# main.net
KiCad netlist of a schematic drawn in Altium Designer
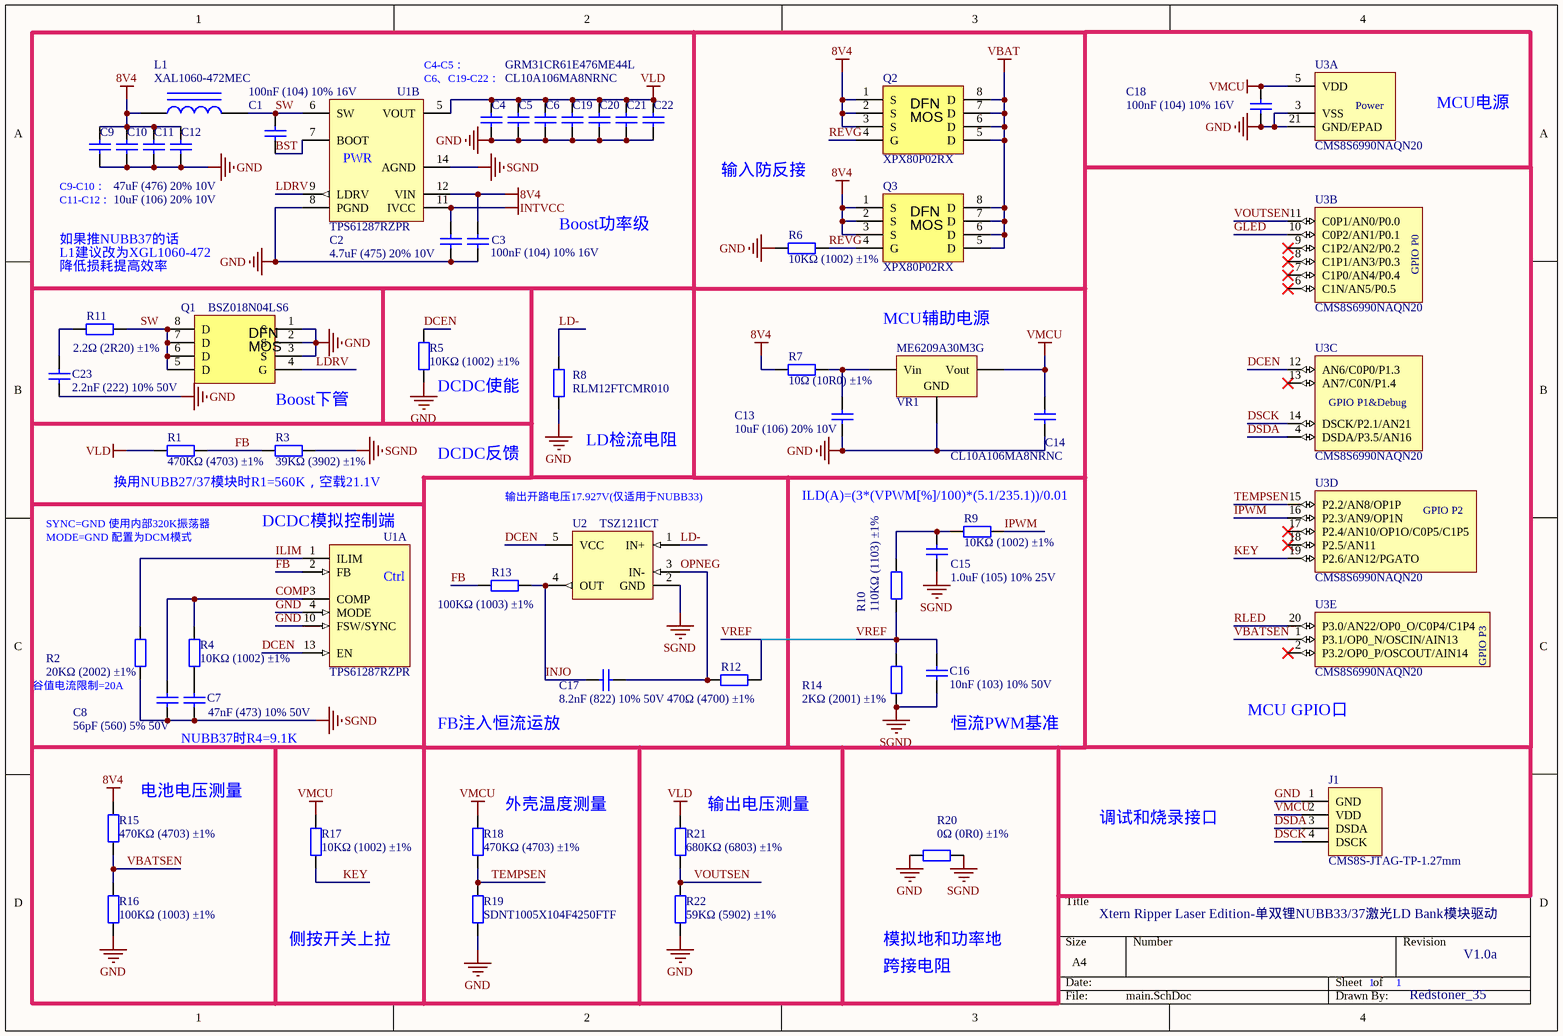
[diagram p0: main.SchDoc]

(export (version "E")
  (design (tool "Eeschema 10.0.6"))
  (components
    (comp (ref "C1")
      (value "100nF (104) 10% 16V")
      (footprint "0402_C")
      (description "贴片电容")
      (libsource (lib "Miscellaneous Devices LC") (part "0402 100nF (104) 10% 16V"))
    )
    (comp (ref "C2")
      (value "4.7uF (475) 20% 10V")
      (footprint "0402_C")
      (description "贴片电容")
      (libsource (lib "Miscellaneous Devices LC") (part "0402 4.7uF (475) 20% 10V"))
    )
    (comp (ref "C3")
      (value "100nF (104) 10% 16V")
      (footprint "0402_C")
      (description "贴片电容")
      (libsource (lib "Miscellaneous Devices LC") (part "0402 100nF (104) 10% 16V"))
    )
    (comp (ref "C4")
      (value "GRM31CR61E476ME44L")
      (footprint "1206C")
      (description "村田1206 MLCC 25V 47uF± 20% X5R")
      (fields (field (name "PUBLISHER") "Altium Limited"))
      (libsource (lib "山猫的集成库20190318") (part "Cap"))
    )
    (comp (ref "C5")
      (value "GRM31CR61E476ME44L")
      (footprint "1206C")
      (description "村田1206 MLCC 25V 47uF± 20% X5R")
      (fields (field (name "PUBLISHER") "Altium Limited"))
      (libsource (lib "山猫的集成库20190318") (part "Cap"))
    )
    (comp (ref "C6")
      (value "CL10A106MA8NRNC")
      (footprint "0603_C")
      (description "三星MLCC X5R 10uF ±20% 25V 0603封装")
      (libsource (lib "Miscellaneous Devices LC") (part "0603 10uF (106) 10% 10V"))
    )
    (comp (ref "C7")
      (value "47nF (473) 10% 50V")
      (footprint "0402_C")
      (description "贴片电容")
      (libsource (lib "Miscellaneous Devices LC") (part "0402 100nF (104) 10% 16V"))
    )
    (comp (ref "C8")
      (value "56pF (560) 5% 50V")
      (footprint "0402_C")
      (description "贴片电容")
      (libsource (lib "Miscellaneous Devices LC") (part "0402 56pF (560) 5% 50V"))
    )
    (comp (ref "C9")
      (value "10uF (106) 20% 10V")
      (footprint "0402_C")
      (description "贴片电容")
      (libsource (lib "Miscellaneous Devices LC") (part "0402 10uF (106) 20% 6.3V"))
    )
    (comp (ref "C10")
      (value "10uF (106) 20% 10V")
      (footprint "0402_C")
      (description "贴片电容")
      (libsource (lib "Miscellaneous Devices LC") (part "0402 10uF (106) 20% 6.3V"))
    )
    (comp (ref "C11")
      (value "47uF (476) 20% 10V")
      (footprint "0805_C")
      (description "贴片电容")
      (libsource (lib "Miscellaneous Devices LC") (part "0805 22uF (226) 20% 25V"))
    )
    (comp (ref "C12")
      (value "47uF (226) 20% 10V")
      (footprint "0805_C")
      (description "贴片电容")
      (libsource (lib "Miscellaneous Devices LC") (part "0805 22uF (226) 20% 25V"))
    )
    (comp (ref "C13")
      (value "10uF (106) 20% 10V")
      (footprint "0402_C")
      (description "贴片电容")
      (libsource (lib "Miscellaneous Devices LC") (part "0402 10uF (106) 20% 6.3V"))
    )
    (comp (ref "C14")
      (value "CL10A106MA8NRNC")
      (footprint "0603_C")
      (description "三星MLCC X5R 10uF ±20% 25V 0603封装")
      (libsource (lib "Miscellaneous Devices LC") (part "0603 10uF (106) 10% 10V"))
    )
    (comp (ref "C15")
      (value "1.0uF (105) 10% 25V")
      (footprint "0402_C")
      (description "贴片电容")
      (libsource (lib "Miscellaneous Devices LC") (part "0402 1.0uF (105) 10% 25V"))
    )
    (comp (ref "C16")
      (value "10nF (103) 10% 50V")
      (footprint "0402_C")
      (description "贴片电容")
      (libsource (lib "Miscellaneous Devices LC") (part "0402 22nF (223) 10% 50V"))
    )
    (comp (ref "C17")
      (value "8.2nF (822) 10% 50V")
      (footprint "0402_C")
      (description "贴片电容")
      (libsource (lib "Miscellaneous Devices LC") (part "0402 22nF (223) 10% 50V"))
    )
    (comp (ref "C18")
      (value "100nF (104) 10% 16V")
      (footprint "0402_C")
      (description "贴片电容")
      (libsource (lib "Miscellaneous Devices LC") (part "0402 100nF (104) 10% 16V"))
    )
    (comp (ref "C19")
      (value "CL10A106MA8NRNC")
      (footprint "0603_C")
      (description "三星MLCC X5R 10uF ±20% 25V 0603封装")
      (libsource (lib "Miscellaneous Devices LC") (part "0603 10uF (106) 10% 10V"))
    )
    (comp (ref "C20")
      (value "CL10A106MA8NRNC")
      (footprint "0603_C")
      (description "三星MLCC X5R 10uF ±20% 25V 0603封装")
      (libsource (lib "Miscellaneous Devices LC") (part "0603 10uF (106) 10% 10V"))
    )
    (comp (ref "C21")
      (value "CL10A106MA8NRNC")
      (footprint "0603_C")
      (description "三星MLCC X5R 10uF ±20% 25V 0603封装")
      (libsource (lib "Miscellaneous Devices LC") (part "0603 10uF (106) 10% 10V"))
    )
    (comp (ref "C22")
      (value "CL10A106MA8NRNC")
      (footprint "0603_C")
      (description "三星MLCC X5R 10uF ±20% 25V 0603封装")
      (libsource (lib "Miscellaneous Devices LC") (part "0603 10uF (106) 10% 10V"))
    )
    (comp (ref "C23")
      (value "2.2nF (222) 10% 50V")
      (footprint "0402_C")
      (description "贴片电容")
      (libsource (lib "Miscellaneous Devices LC") (part "0402 2.2nF (222) 10% 50V"))
    )
    (comp (ref "J1")
      (value "CMS8S-JTAG-TP-1.27mm")
      (footprint "CMS8S-JTAG-TP-2x2-P1.27")
      (description "面向CMS8S6990NA单片机的调试贴片触点，并不是元器件实物")
      (libsource (lib "custom") (part "CMS8S-JTAG-TP-1.27mm"))
    )
    (comp (ref "L1")
      (value "XAL1060-472MEC")
      (footprint "XAL1060-472ME-Lifted")
      (description "线艺一体成型模压电感，9.8mΩ DCR 25A饱和电流 4.7uH±20%电感量 10*11*6mm尺寸")
      (fields (field (name "PUBLISHER") "Altium Limited"))
      (libsource (lib "Miscellaneous Devices") (part "Inductor Iron"))
    )
    (comp (ref "Q1")
      (value "BSZ018N04LS6")
      (footprint "DFN-8_L3.0-W3.0-P0.65-BL")
      (description "PDFN3x3 30V 50A N沟道MOSFET")
      (libsource (lib "") (part "SON/DFN5x6 MOS_1"))
    )
    (comp (ref "Q2")
      (value "XPX80P02RX")
      (footprint "DFN-8_L3.0-W3.0-P0.65-BL")
      (description "PDFN3x3 30V 50A N沟道MOSFET")
      (libsource (lib "custom") (part "SON/DFN5x6 MOS"))
    )
    (comp (ref "Q3")
      (value "XPX80P02RX")
      (footprint "DFN-8_L3.0-W3.0-P0.65-BL")
      (description "PDFN3x3 30V 50A N沟道MOSFET")
      (libsource (lib "custom") (part "SON/DFN5x6 MOS"))
    )
    (comp (ref "R1")
      (value "470KΩ (4703) ±1%")
      (footprint "0402_R")
      (description "贴片电阻")
      (libsource (lib "Miscellaneous Devices LC") (part "0402 470KΩ (4703) 1%"))
    )
    (comp (ref "R2")
      (value "20KΩ (2002) ±1%")
      (footprint "0402_R")
      (description "贴片电阻")
      (libsource (lib "Miscellaneous Devices LC") (part "0402 20KΩ (2002) 1%"))
    )
    (comp (ref "R3")
      (value "39KΩ (3902) ±1%")
      (footprint "0402_R")
      (description "贴片电阻")
      (libsource (lib "Miscellaneous Devices LC") (part "0402 39KΩ (3902) 1%"))
    )
    (comp (ref "R4")
      (value "10KΩ (1002) ±1%")
      (footprint "0402_R")
      (description "贴片电阻")
      (libsource (lib "Miscellaneous Devices LC") (part "0402 12KΩ (1202) 1%"))
    )
    (comp (ref "R5")
      (value "10KΩ (1002) ±1%")
      (footprint "0402_R")
      (description "贴片电阻")
      (libsource (lib "Miscellaneous Devices LC") (part "0402 10KΩ (1002) 1%"))
    )
    (comp (ref "R6")
      (value "10KΩ (1002) ±1%")
      (footprint "0402_R")
      (description "贴片电阻")
      (libsource (lib "") (part "0402 10KΩ (1002) 1%_2"))
    )
    (comp (ref "R7")
      (value "10Ω (10R0) ±1%")
      (footprint "0402_R")
      (description "贴片电阻")
      (libsource (lib "Miscellaneous Devices LC") (part "0402 10Ω (10R0) 1%"))
    )
    (comp (ref "R8")
      (value "RLM12FTCMR010")
      (footprint "1206_R")
      (description "10mΩ ±1% 1W 1206封装合金检流电阻")
      (libsource (lib "Miscellaneous Devices LC") (part "1206 0Ω (0R0) 1%"))
    )
    (comp (ref "R9")
      (value "10KΩ (1002) ±1%")
      (footprint "0402_R")
      (description "贴片电阻")
      (libsource (lib "") (part "0402 10KΩ (1002) 1%_1"))
    )
    (comp (ref "R10")
      (value "110KΩ (1103) ±1%")
      (footprint "0402_R")
      (description "贴片电阻")
      (libsource (lib "Miscellaneous Devices LC") (part "0402 75KΩ (7502) 1%"))
    )
    (comp (ref "R11")
      (value "2.2Ω (2R20) ±1%")
      (footprint "0603_R")
      (description "贴片电阻")
      (libsource (lib "Miscellaneous Devices LC") (part "0603 2.2Ω (2R20) 1%"))
    )
    (comp (ref "R12")
      (value "470Ω (4700) ±1%")
      (footprint "0402_R")
      (description "贴片电阻")
      (libsource (lib "Miscellaneous Devices LC") (part "0402 470Ω (4700) 1%"))
    )
    (comp (ref "R13")
      (value "100KΩ (1003) ±1%")
      (footprint "0402_R")
      (description "贴片电阻")
      (libsource (lib "Miscellaneous Devices LC") (part "0402 100KΩ (1003) 1%"))
    )
    (comp (ref "R14")
      (value "2KΩ (2001) ±1%")
      (footprint "0402_R")
      (description "贴片电阻")
      (libsource (lib "Miscellaneous Devices LC") (part "0402 10KΩ (1002) 1%"))
    )
    (comp (ref "R15")
      (value "470KΩ (4703) ±1%")
      (footprint "0402_R")
      (description "贴片电阻")
      (libsource (lib "") (part "0402 470KΩ (4703) 1%_1"))
    )
    (comp (ref "R16")
      (value "100KΩ (1003) ±1%")
      (footprint "0402_R")
      (description "贴片电阻")
      (libsource (lib "") (part "0402 100KΩ (1003) 1%_1"))
    )
    (comp (ref "R17")
      (value "10KΩ (1002) ±1%")
      (footprint "0402_R")
      (description "贴片电阻")
      (libsource (lib "Miscellaneous Devices LC") (part "0402 10KΩ (1002) 1%"))
    )
    (comp (ref "R18")
      (value "470KΩ (4703) ±1%")
      (footprint "0402_R")
      (description "贴片电阻")
      (libsource (lib "") (part "0402 470KΩ (4703) 1%_1"))
    )
    (comp (ref "R19")
      (value "SDNT1005X104F4250FTF")
      (footprint "0402_R")
      (description "贴片热敏电阻0402 B4250 100K ±1%")
      (libsource (lib "Miscellaneous Devices LC") (part "0402 200KΩ (2003) 1%"))
    )
    (comp (ref "R20")
      (value "0Ω (0R0) ±1%")
      (footprint "0402_R")
      (description "贴片电阻")
      (libsource (lib "Miscellaneous Devices LC") (part "0402 0Ω (0R0) 1%"))
    )
    (comp (ref "R21")
      (value "680KΩ (6803) ±1%")
      (footprint "0402_R")
      (description "贴片电阻")
      (libsource (lib "") (part "0402 470KΩ (4703) 1%_1"))
    )
    (comp (ref "R22")
      (value "59KΩ (5902) ±1%")
      (footprint "0402_R")
      (description "贴片电阻")
      (libsource (lib "Miscellaneous Devices LC") (part "0402 68KΩ (6802) 1%"))
    )
    (comp (ref "U1")
      (value "TPS61287RZPR")
      (footprint "RZP0014A-TPS61287")
      (description "Synchronous Boost Converter with Stackable Multi-Phase Function")
      (libsource (lib "custom") (part "TPS61287"))
    )
    (comp (ref "U2")
      (value "TSZ121ICT")
      (footprint "SC70-5")
      (description "CMOS超小型0漂移斩波结构运算放大器，SC70-5封装，400KHz GBW")
      (libsource (lib "custom") (part "LMV321IDCKR"))
    )
    (comp (ref "U3")
      (value "CMS8S6990NAQN20")
      (footprint "QFN40P300X300X800_HS-21N")
      (description "增强型闪存1T 8051单片机，16KB Flash 256+1K XRAM，QFN3x3-20P封装")
      (libsource (lib "custom") (part "CM8S6990NA-QFN20"))
    )
    (comp (ref "VR1")
      (value "ME6209A30M3G")
      (footprint "SOT-23-3L")
      (description "低压差线性稳压(LDO)")
      (libsource (lib "Miscellaneous Devices LC") (part "SOT-23 XC6206P332MR"))
    )
  )
  (nets
    (net (code "1") (name "/BST") (class "Default")
      (node (ref "C1") (pin "1") (pinfunction "1_1") (pintype "passive"))
      (node (ref "U1") (pin "7") (pinfunction "BOOT_7") (pintype "power_in"))
    )
    (net (code "2") (name "/COMP") (class "Default")
      (node (ref "C8") (pin "2") (pinfunction "2_2") (pintype "passive"))
      (node (ref "R4") (pin "2") (pinfunction "2_2") (pintype "passive"))
      (node (ref "U1") (pin "3") (pinfunction "COMP_3") (pintype "passive"))
    )
    (net (code "3") (name "/DCEN") (class "Default")
      (node (ref "R5") (pin "2") (pinfunction "2_2") (pintype "passive"))
      (node (ref "U1") (pin "13") (pinfunction "EN_13") (pintype "input"))
      (node (ref "U2") (pin "5") (pinfunction "VCC_5") (pintype "power_in"))
      (node (ref "U3") (pin "12") (pinfunction "AN6/C0P0/P1.3_12") (pintype "bidirectional"))
    )
    (net (code "4") (name "/DSCK") (class "Default")
      (node (ref "J1") (pin "4") (pinfunction "DSCK_4") (pintype "passive"))
      (node (ref "U3") (pin "14") (pinfunction "DSCK/P2.1/AN21_14") (pintype "bidirectional"))
    )
    (net (code "5") (name "/DSDA") (class "Default")
      (node (ref "J1") (pin "3") (pinfunction "DSDA_3") (pintype "passive"))
      (node (ref "U3") (pin "4") (pinfunction "DSDA/P3.5/AN16_4") (pintype "bidirectional"))
    )
    (net (code "6") (name "/FB") (class "Default")
      (node (ref "R1") (pin "2") (pinfunction "2_2") (pintype "passive"))
      (node (ref "R13") (pin "1") (pinfunction "1_1") (pintype "passive"))
      (node (ref "R3") (pin "2") (pinfunction "2_2") (pintype "passive"))
      (node (ref "U1") (pin "2") (pinfunction "FB_2") (pintype "input"))
    )
    (net (code "7") (name "/GLED") (class "Default")
      (node (ref "U3") (pin "10") (pinfunction "C0P2/AN1/P0.1_10") (pintype "bidirectional"))
    )
    (net (code "8") (name "/ILIM") (class "Default")
      (node (ref "R2") (pin "1") (pinfunction "1_1") (pintype "passive"))
      (node (ref "U1") (pin "1") (pinfunction "ILIM_1") (pintype "passive"))
    )
    (net (code "9") (name "/INJO") (class "Default")
      (node (ref "C17") (pin "1") (pinfunction "1_1") (pintype "passive"))
      (node (ref "R13") (pin "2") (pinfunction "2_2") (pintype "passive"))
      (node (ref "U2") (pin "4") (pinfunction "OUT_4") (pintype "output"))
    )
    (net (code "10") (name "/IPWM") (class "Default")
      (node (ref "R9") (pin "1") (pinfunction "1_1") (pintype "passive"))
      (node (ref "U3") (pin "16") (pinfunction "P2.3/AN9/OP1N_16") (pintype "bidirectional"))
    )
    (net (code "11") (name "/KEY") (class "Default")
      (node (ref "R17") (pin "1") (pinfunction "1_1") (pintype "passive"))
      (node (ref "U3") (pin "19") (pinfunction "P2.6/AN12/PGATO_19") (pintype "bidirectional"))
    )
    (net (code "12") (name "/LD-") (class "Default")
      (node (ref "R8") (pin "2") (pinfunction "2_2") (pintype "passive"))
      (node (ref "U2") (pin "1") (pinfunction "IN+_1") (pintype "input"))
    )
    (net (code "13") (name "/LDRV") (class "Default")
      (node (ref "Q1") (pin "4") (pinfunction "G_4") (pintype "passive"))
      (node (ref "U1") (pin "9") (pinfunction "LDRV_9") (pintype "output"))
    )
    (net (code "14") (name "/OPNEG") (class "Default")
      (node (ref "C17") (pin "2") (pinfunction "2_2") (pintype "passive"))
      (node (ref "R12") (pin "1") (pinfunction "1_1") (pintype "passive"))
      (node (ref "U2") (pin "3") (pinfunction "IN-_3") (pintype "input"))
    )
    (net (code "15") (name "/REVG") (class "Default")
      (node (ref "Q2") (pin "4") (pinfunction "G_4") (pintype "passive"))
      (node (ref "Q3") (pin "4") (pinfunction "G_4") (pintype "passive"))
      (node (ref "R6") (pin "2") (pinfunction "2_2") (pintype "passive"))
    )
    (net (code "16") (name "/RLED") (class "Default")
      (node (ref "U3") (pin "20") (pinfunction "P3.0/AN22/OP0_O/C0P4/C1P4_20") (pintype "bidirectional"))
    )
    (net (code "17") (name "/SW") (class "Default")
      (node (ref "C1") (pin "2") (pinfunction "2_2") (pintype "passive"))
      (node (ref "L1") (pin "2") (pinfunction "2_2") (pintype "passive"))
      (node (ref "Q1") (pin "5") (pinfunction "D_5") (pintype "passive"))
      (node (ref "Q1") (pin "6") (pinfunction "D_6") (pintype "passive"))
      (node (ref "Q1") (pin "7") (pinfunction "D_7") (pintype "passive"))
      (node (ref "Q1") (pin "8") (pinfunction "D_8") (pintype "passive"))
      (node (ref "R11") (pin "2") (pinfunction "2_2") (pintype "passive"))
      (node (ref "U1") (pin "6") (pinfunction "SW_6") (pintype "power_in"))
    )
    (net (code "18") (name "/TEMPSEN") (class "Default")
      (node (ref "R18") (pin "1") (pinfunction "1_1") (pintype "passive"))
      (node (ref "R19") (pin "2") (pinfunction "2_2") (pintype "passive"))
      (node (ref "U3") (pin "15") (pinfunction "P2.2/AN8/OP1P_15") (pintype "bidirectional"))
    )
    (net (code "19") (name "/VBATSEN") (class "Default")
      (node (ref "R15") (pin "1") (pinfunction "1_1") (pintype "passive"))
      (node (ref "R16") (pin "2") (pinfunction "2_2") (pintype "passive"))
      (node (ref "U3") (pin "1") (pinfunction "P3.1/OP0_N/OSCIN/AIN13_1") (pintype "bidirectional"))
    )
    (net (code "20") (name "/VOUTSEN") (class "Default")
      (node (ref "R21") (pin "1") (pinfunction "1_1") (pintype "passive"))
      (node (ref "R22") (pin "2") (pinfunction "2_2") (pintype "passive"))
      (node (ref "U3") (pin "11") (pinfunction "C0P1/AN0/P0.0_11") (pintype "bidirectional"))
    )
    (net (code "21") (name "/VREF") (class "Default")
      (node (ref "C16") (pin "2") (pinfunction "2_2") (pintype "passive"))
      (node (ref "R10") (pin "1") (pinfunction "1_1") (pintype "passive"))
      (node (ref "R12") (pin "2") (pinfunction "2_2") (pintype "passive"))
      (node (ref "R14") (pin "2") (pinfunction "2_2") (pintype "passive"))
    )
    (net (code "22") (name "8V4") (class "Default")
      (node (ref "C10") (pin "2") (pinfunction "2_2") (pintype "passive"))
      (node (ref "C11") (pin "2") (pinfunction "2_2") (pintype "passive"))
      (node (ref "C12") (pin "2") (pinfunction "2_2") (pintype "passive"))
      (node (ref "C3") (pin "2") (pinfunction "2_2") (pintype "passive"))
      (node (ref "C9") (pin "2") (pinfunction "2_2") (pintype "passive"))
      (node (ref "L1") (pin "1") (pinfunction "1_1") (pintype "passive"))
      (node (ref "Q2") (pin "1") (pinfunction "S_1") (pintype "passive"))
      (node (ref "Q2") (pin "2") (pinfunction "S_2") (pintype "passive"))
      (node (ref "Q2") (pin "3") (pinfunction "S_3") (pintype "passive"))
      (node (ref "Q3") (pin "1") (pinfunction "S_1") (pintype "passive"))
      (node (ref "Q3") (pin "2") (pinfunction "S_2") (pintype "passive"))
      (node (ref "Q3") (pin "3") (pinfunction "S_3") (pintype "passive"))
      (node (ref "R15") (pin "2") (pinfunction "2_2") (pintype "passive"))
      (node (ref "R7") (pin "1") (pinfunction "1_1") (pintype "passive"))
      (node (ref "U1") (pin "12") (pinfunction "VIN_12") (pintype "power_in"))
    )
    (net (code "23") (name "GND") (class "Default")
      (node (ref "C10") (pin "1") (pinfunction "1_1") (pintype "passive"))
      (node (ref "C11") (pin "1") (pinfunction "1_1") (pintype "passive"))
      (node (ref "C12") (pin "1") (pinfunction "1_1") (pintype "passive"))
      (node (ref "C13") (pin "1") (pinfunction "1_1") (pintype "passive"))
      (node (ref "C14") (pin "1") (pinfunction "1_1") (pintype "passive"))
      (node (ref "C18") (pin "1") (pinfunction "1_1") (pintype "passive"))
      (node (ref "C19") (pin "1") (pinfunction "1_1") (pintype "passive"))
      (node (ref "C2") (pin "1") (pinfunction "1_1") (pintype "passive"))
      (node (ref "C20") (pin "1") (pinfunction "1_1") (pintype "passive"))
      (node (ref "C21") (pin "1") (pinfunction "1_1") (pintype "passive"))
      (node (ref "C22") (pin "1") (pinfunction "1_1") (pintype "passive"))
      (node (ref "C23") (pin "1") (pinfunction "1_1") (pintype "passive"))
      (node (ref "C3") (pin "1") (pinfunction "1_1") (pintype "passive"))
      (node (ref "C4") (pin "1") (pinfunction "1_1") (pintype "passive"))
      (node (ref "C5") (pin "1") (pinfunction "1_1") (pintype "passive"))
      (node (ref "C6") (pin "1") (pinfunction "1_1") (pintype "passive"))
      (node (ref "C9") (pin "1") (pinfunction "1_1") (pintype "passive"))
      (node (ref "J1") (pin "1") (pinfunction "GND_1") (pintype "passive"))
      (node (ref "Q1") (pin "1") (pinfunction "S_1") (pintype "passive"))
      (node (ref "Q1") (pin "2") (pinfunction "S_2") (pintype "passive"))
      (node (ref "Q1") (pin "3") (pinfunction "S_3") (pintype "passive"))
      (node (ref "R16") (pin "1") (pinfunction "1_1") (pintype "passive"))
      (node (ref "R19") (pin "1") (pinfunction "1_1") (pintype "passive"))
      (node (ref "R20") (pin "1") (pinfunction "1_1") (pintype "passive"))
      (node (ref "R22") (pin "1") (pinfunction "1_1") (pintype "passive"))
      (node (ref "R5") (pin "1") (pinfunction "1_1") (pintype "passive"))
      (node (ref "R6") (pin "1") (pinfunction "1_1") (pintype "passive"))
      (node (ref "R8") (pin "1") (pinfunction "1_1") (pintype "passive"))
      (node (ref "U1") (pin "10") (pinfunction "FSW/SYNC_10") (pintype "input"))
      (node (ref "U1") (pin "4") (pinfunction "MODE_4") (pintype "input"))
      (node (ref "U1") (pin "8") (pinfunction "PGND_8") (pintype "power_in"))
      (node (ref "U3") (pin "21") (pinfunction "GND/EPAD_21") (pintype "power_in"))
      (node (ref "U3") (pin "3") (pinfunction "VSS_3") (pintype "power_in"))
      (node (ref "VR1") (pin "1") (pinfunction "GND_1") (pintype "passive"))
    )
    (net (code "24") (name "INTVCC") (class "Default")
      (node (ref "C2") (pin "2") (pinfunction "2_2") (pintype "passive"))
      (node (ref "U1") (pin "11") (pinfunction "IVCC_11") (pintype "power_in"))
    )
    (net (code "25") (name "Net-(C7-Pad2)") (class "Default")
      (node (ref "C7") (pin "2") (pinfunction "2_2") (pintype "passive"))
      (node (ref "R4") (pin "1") (pinfunction "1_1") (pintype "passive"))
    )
    (net (code "26") (name "Net-(C15-Pad2)") (class "Default")
      (node (ref "C15") (pin "2") (pinfunction "2_2") (pintype "passive"))
      (node (ref "R10") (pin "2") (pinfunction "2_2") (pintype "passive"))
      (node (ref "R9") (pin "2") (pinfunction "2_2") (pintype "passive"))
    )
    (net (code "27") (name "Net-(C23-Pad2)") (class "Default")
      (node (ref "C23") (pin "2") (pinfunction "2_2") (pintype "passive"))
      (node (ref "R11") (pin "1") (pinfunction "1_1") (pintype "passive"))
    )
    (net (code "28") (name "Net-(VR1-Vin)") (class "Default")
      (node (ref "C13") (pin "2") (pinfunction "2_2") (pintype "passive"))
      (node (ref "R7") (pin "2") (pinfunction "2_2") (pintype "passive"))
      (node (ref "VR1") (pin "3") (pinfunction "Vin_3") (pintype "passive"))
    )
    (net (code "29") (name "SGND") (class "Default")
      (node (ref "C15") (pin "1") (pinfunction "1_1") (pintype "passive"))
      (node (ref "C16") (pin "1") (pinfunction "1_1") (pintype "passive"))
      (node (ref "C7") (pin "1") (pinfunction "1_1") (pintype "passive"))
      (node (ref "C8") (pin "1") (pinfunction "1_1") (pintype "passive"))
      (node (ref "R14") (pin "1") (pinfunction "1_1") (pintype "passive"))
      (node (ref "R2") (pin "2") (pinfunction "2_2") (pintype "passive"))
      (node (ref "R20") (pin "2") (pinfunction "2_2") (pintype "passive"))
      (node (ref "R3") (pin "1") (pinfunction "1_1") (pintype "passive"))
      (node (ref "U1") (pin "14") (pinfunction "AGND_14") (pintype "power_in"))
      (node (ref "U2") (pin "2") (pinfunction "GND_2") (pintype "power_in"))
    )
    (net (code "30") (name "VBAT") (class "Default")
      (node (ref "Q2") (pin "5") (pinfunction "D_5") (pintype "passive"))
      (node (ref "Q2") (pin "6") (pinfunction "D_6") (pintype "passive"))
      (node (ref "Q2") (pin "7") (pinfunction "D_7") (pintype "passive"))
      (node (ref "Q2") (pin "8") (pinfunction "D_8") (pintype "passive"))
      (node (ref "Q3") (pin "5") (pinfunction "D_5") (pintype "passive"))
      (node (ref "Q3") (pin "6") (pinfunction "D_6") (pintype "passive"))
      (node (ref "Q3") (pin "7") (pinfunction "D_7") (pintype "passive"))
      (node (ref "Q3") (pin "8") (pinfunction "D_8") (pintype "passive"))
    )
    (net (code "31") (name "VLD") (class "Default")
      (node (ref "C19") (pin "2") (pinfunction "2_2") (pintype "passive"))
      (node (ref "C20") (pin "2") (pinfunction "2_2") (pintype "passive"))
      (node (ref "C21") (pin "2") (pinfunction "2_2") (pintype "passive"))
      (node (ref "C22") (pin "2") (pinfunction "2_2") (pintype "passive"))
      (node (ref "C4") (pin "2") (pinfunction "2_2") (pintype "passive"))
      (node (ref "C5") (pin "2") (pinfunction "2_2") (pintype "passive"))
      (node (ref "C6") (pin "2") (pinfunction "2_2") (pintype "passive"))
      (node (ref "R1") (pin "1") (pinfunction "1_1") (pintype "passive"))
      (node (ref "R21") (pin "2") (pinfunction "2_2") (pintype "passive"))
      (node (ref "U1") (pin "5") (pinfunction "VOUT_5") (pintype "power_in"))
    )
    (net (code "32") (name "VMCU") (class "Default")
      (node (ref "C14") (pin "2") (pinfunction "2_2") (pintype "passive"))
      (node (ref "C18") (pin "2") (pinfunction "2_2") (pintype "passive"))
      (node (ref "J1") (pin "2") (pinfunction "VDD_2") (pintype "passive"))
      (node (ref "R17") (pin "2") (pinfunction "2_2") (pintype "passive"))
      (node (ref "R18") (pin "2") (pinfunction "2_2") (pintype "passive"))
      (node (ref "U3") (pin "5") (pinfunction "VDD_5") (pintype "power_in"))
      (node (ref "VR1") (pin "2") (pinfunction "Vout_2") (pintype "passive"))
    )
    (net (code "33") (name "unconnected-(U3B-C1N{slash}AN5{slash}P0.5-Pad6)") (class "Default")
      (node (ref "U3") (pin "6") (pinfunction "C1N/AN5/P0.5_6") (pintype "bidirectional+no_connect"))
    )
    (net (code "34") (name "unconnected-(U3B-C1P0{slash}AN4{slash}P0.4-Pad7)") (class "Default")
      (node (ref "U3") (pin "7") (pinfunction "C1P0/AN4/P0.4_7") (pintype "bidirectional+no_connect"))
    )
    (net (code "35") (name "unconnected-(U3B-C1P1{slash}AN3{slash}P0.3-Pad8)") (class "Default")
      (node (ref "U3") (pin "8") (pinfunction "C1P1/AN3/P0.3_8") (pintype "bidirectional+no_connect"))
    )
    (net (code "36") (name "unconnected-(U3B-C1P2{slash}AN2{slash}P0.2-Pad9)") (class "Default")
      (node (ref "U3") (pin "9") (pinfunction "C1P2/AN2/P0.2_9") (pintype "bidirectional+no_connect"))
    )
    (net (code "37") (name "unconnected-(U3C-AN7{slash}C0N{slash}P1.4-Pad13)") (class "Default")
      (node (ref "U3") (pin "13") (pinfunction "AN7/C0N/P1.4_13") (pintype "bidirectional+no_connect"))
    )
    (net (code "38") (name "unconnected-(U3D-P2.4{slash}AN10{slash}OP1O{slash}C0P5{slash}C1P5-Pad17)") (class "Default")
      (node (ref "U3") (pin "17") (pinfunction "P2.4/AN10/OP1O/C0P5/C1P5_17") (pintype "bidirectional+no_connect"))
    )
    (net (code "39") (name "unconnected-(U3D-P2.5{slash}AN11-Pad18)") (class "Default")
      (node (ref "U3") (pin "18") (pinfunction "P2.5/AN11_18") (pintype "bidirectional+no_connect"))
    )
    (net (code "40") (name "unconnected-(U3E-P3.2{slash}OP0_P{slash}OSCOUT{slash}AIN14-Pad2)") (class "Default")
      (node (ref "U3") (pin "2") (pinfunction "P3.2/OP0_P/OSCOUT/AIN14_2") (pintype "bidirectional+no_connect"))
    )
  )
)
